# eib-64-intan-hs.net
KiCad netlist of a schematic drawn in EAGLE
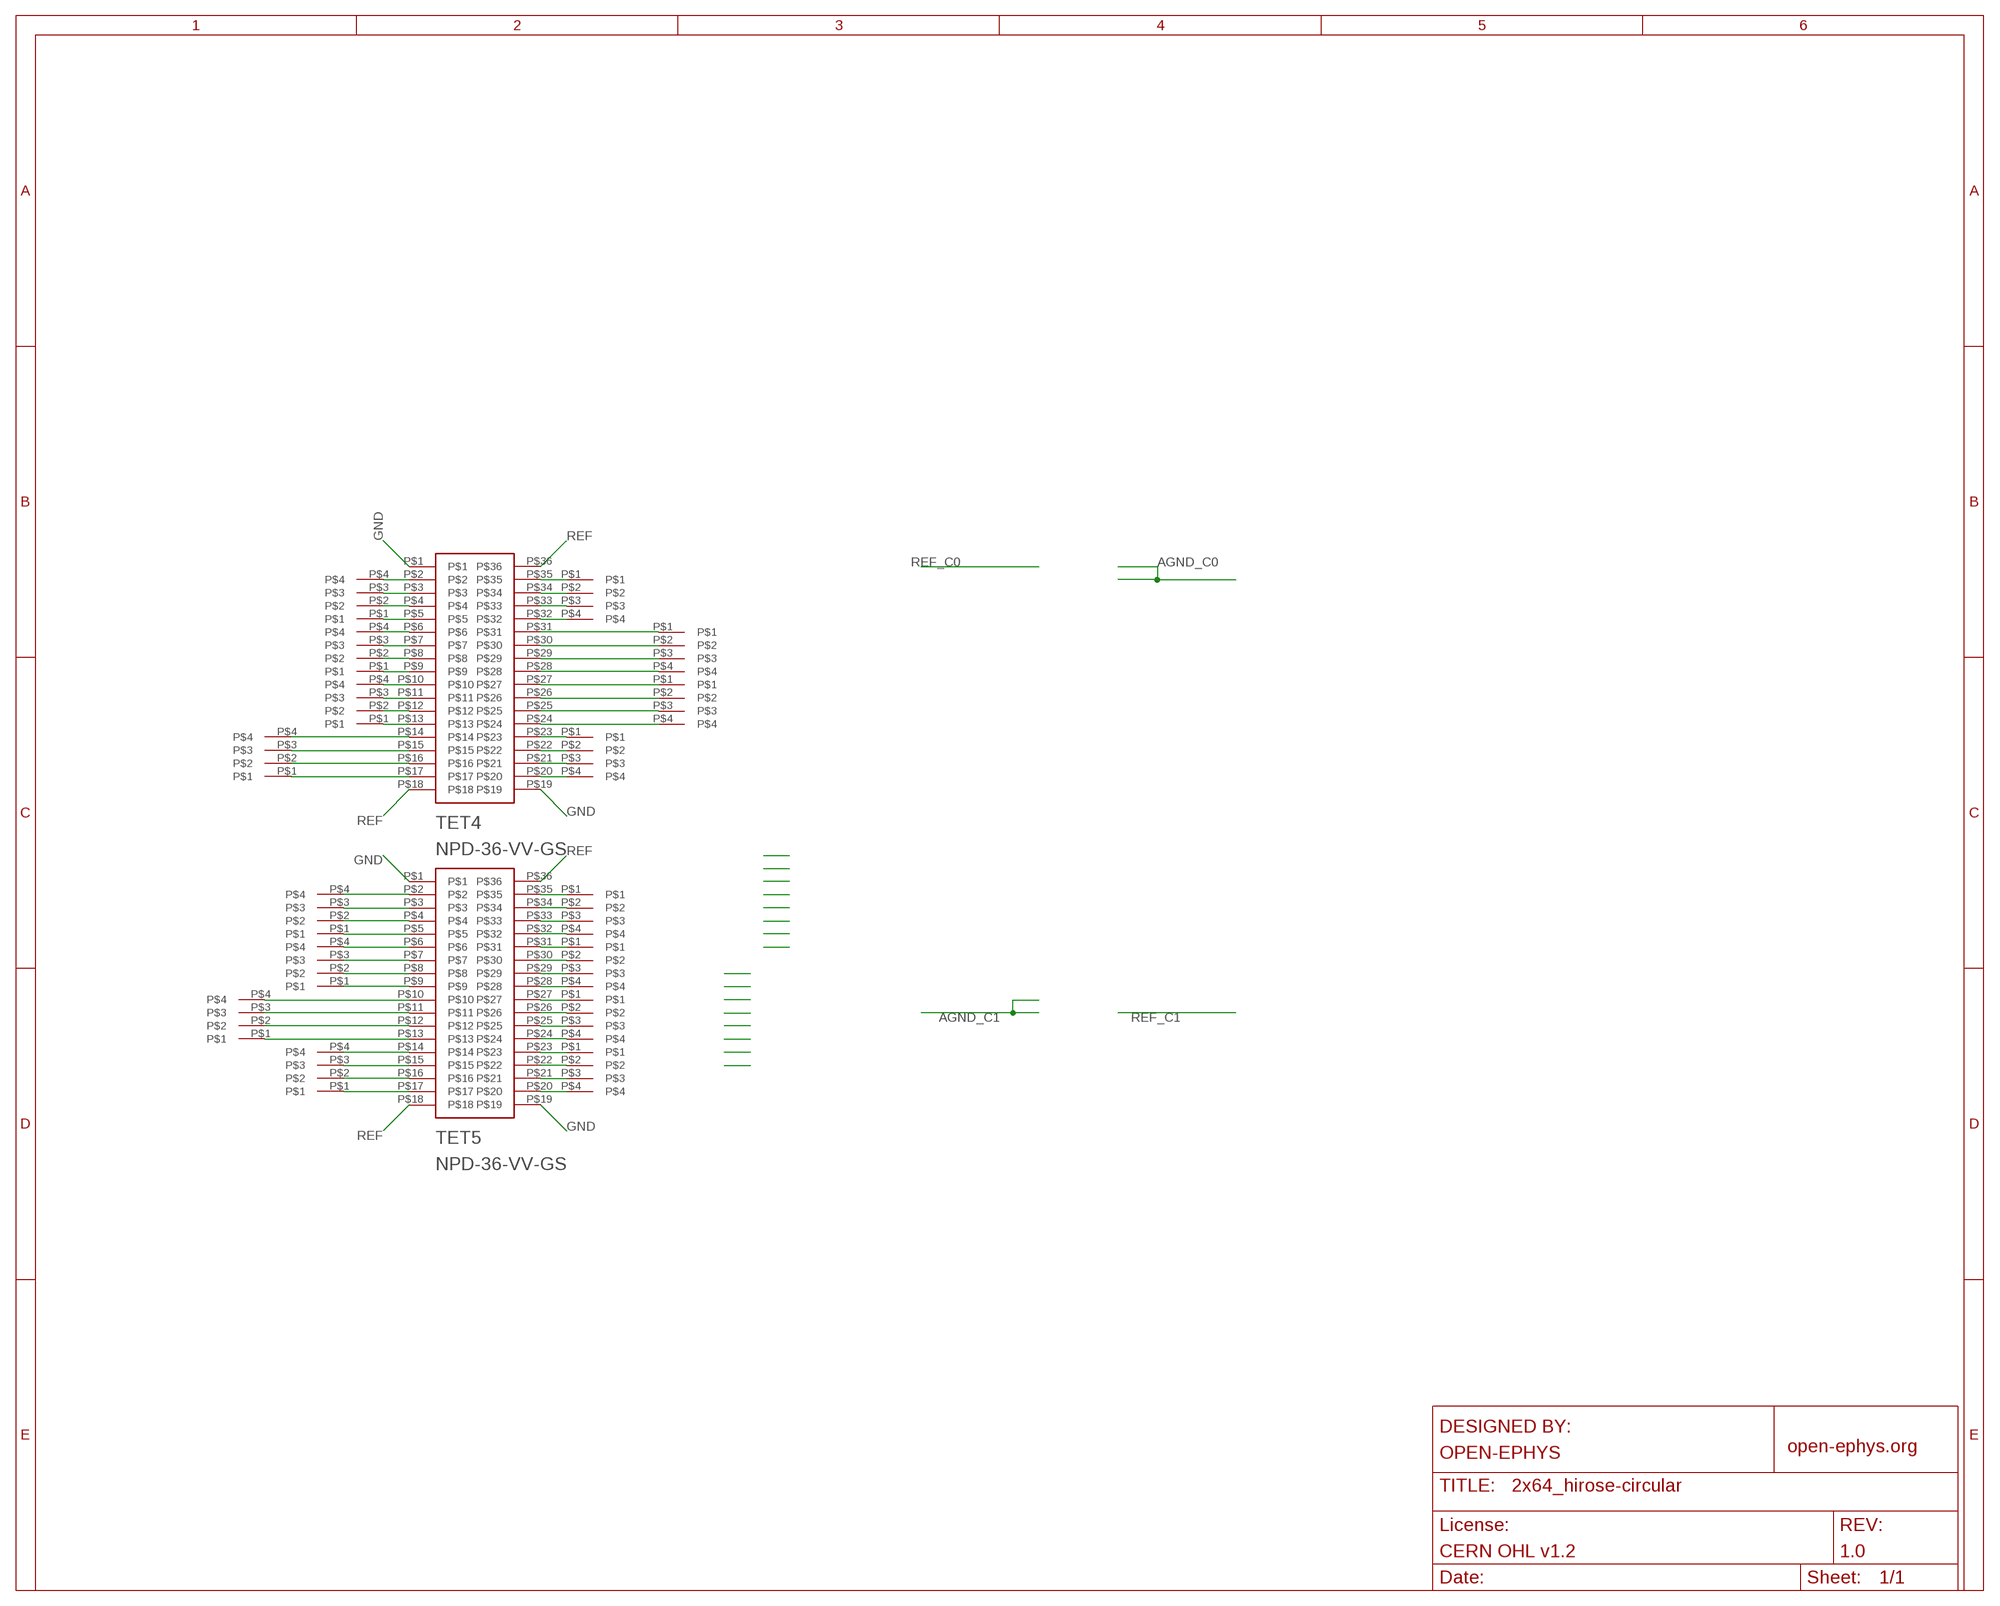
[diagram p0: schematic, sheet 1]

(export (version "E")
  (design (tool "Eeschema 10.0.6"))
  (components
    (comp (ref "TET0")
      (value "0")
      (footprint "eagle-import:TET32")
      (libsource (lib "eagle-import") (part "TET32"))
    )
    (comp (ref "TET1")
      (value "1")
      (footprint "eagle-import:TET32")
      (libsource (lib "eagle-import") (part "TET32"))
    )
    (comp (ref "TET2")
      (value "2")
      (footprint "eagle-import:TET32")
      (libsource (lib "eagle-import") (part "TET32"))
    )
    (comp (ref "TET3")
      (value "3")
      (footprint "eagle-import:TET32")
      (libsource (lib "eagle-import") (part "TET32"))
    )
    (comp (ref "TET4")
      (value "NPD-36-VV-GS")
      (footprint "eagle-import:NPD-36-VV-GS")
      (libsource (lib "eagle-import") (part "NPD-36-VV-GS"))
    )
    (comp (ref "TET5")
      (value "NPD-36-VV-GS")
      (footprint "eagle-import:NPD-36-VV-GS")
      (libsource (lib "eagle-import") (part "NPD-36-VV-GS"))
    )
    (comp (ref "TET8")
      (value "8")
      (footprint "eagle-import:TET32")
      (libsource (lib "eagle-import") (part "TET32"))
    )
    (comp (ref "TET9")
      (value "9")
      (footprint "eagle-import:TET32")
      (libsource (lib "eagle-import") (part "TET32"))
    )
    (comp (ref "TET10")
      (value "10")
      (footprint "eagle-import:TET32")
      (libsource (lib "eagle-import") (part "TET32"))
    )
    (comp (ref "TET11")
      (value "11")
      (footprint "eagle-import:TET32")
      (libsource (lib "eagle-import") (part "TET32"))
    )
    (comp (ref "TET12")
      (value "12")
      (footprint "eagle-import:TET32")
      (libsource (lib "eagle-import") (part "TET32"))
    )
    (comp (ref "TET13")
      (value "13")
      (footprint "eagle-import:TET32")
      (libsource (lib "eagle-import") (part "TET32"))
    )
    (comp (ref "TET14")
      (value "14")
      (footprint "eagle-import:TET32")
      (libsource (lib "eagle-import") (part "TET32"))
    )
    (comp (ref "TET15")
      (value "15")
      (footprint "eagle-import:TET32")
      (libsource (lib "eagle-import") (part "TET32"))
    )
    (comp (ref "TET20")
      (value "20")
      (footprint "eagle-import:TET32")
      (libsource (lib "eagle-import") (part "TET32"))
    )
    (comp (ref "TET21")
      (value "21")
      (footprint "eagle-import:TET32")
      (libsource (lib "eagle-import") (part "TET32"))
    )
    (comp (ref "TET22")
      (value "22")
      (footprint "eagle-import:TET32")
      (libsource (lib "eagle-import") (part "TET32"))
    )
    (comp (ref "TET23")
      (value "23")
      (footprint "eagle-import:TET32")
      (libsource (lib "eagle-import") (part "TET32"))
    )
  )
  (nets
    (net (code "3") (name "/GND") (class "Default")
      (node (ref "TET4") (pin "P$1") (pinfunction "P$1_P$1") (pintype "bidirectional"))
      (node (ref "TET4") (pin "P$19") (pinfunction "P$19_P$19") (pintype "bidirectional"))
      (node (ref "TET5") (pin "P$1") (pinfunction "P$1_P$1") (pintype "bidirectional"))
      (node (ref "TET5") (pin "P$19") (pinfunction "P$19_P$19") (pintype "bidirectional"))
    )
    (net (code "4") (name "/REF") (class "Default")
      (node (ref "TET4") (pin "P$18") (pinfunction "P$18_P$18") (pintype "bidirectional"))
      (node (ref "TET4") (pin "P$36") (pinfunction "P$36_P$36") (pintype "bidirectional"))
      (node (ref "TET5") (pin "P$18") (pinfunction "P$18_P$18") (pintype "bidirectional"))
      (node (ref "TET5") (pin "P$36") (pinfunction "P$36_P$36") (pintype "bidirectional"))
    )
    (net (code "7") (name "Net-(TET0-PadP$1)") (class "Default")
      (node (ref "TET0") (pin "P$1") (pinfunction "P$1_P$1") (pintype "bidirectional"))
      (node (ref "TET4") (pin "P$9") (pinfunction "P$9_P$9") (pintype "bidirectional"))
    )
    (net (code "8") (name "Net-(TET0-PadP$2)") (class "Default")
      (node (ref "TET0") (pin "P$2") (pinfunction "P$2_P$2") (pintype "bidirectional"))
      (node (ref "TET4") (pin "P$8") (pinfunction "P$8_P$8") (pintype "bidirectional"))
    )
    (net (code "9") (name "Net-(TET0-PadP$3)") (class "Default")
      (node (ref "TET0") (pin "P$3") (pinfunction "P$3_P$3") (pintype "bidirectional"))
      (node (ref "TET4") (pin "P$7") (pinfunction "P$7_P$7") (pintype "bidirectional"))
    )
    (net (code "10") (name "Net-(TET0-PadP$4)") (class "Default")
      (node (ref "TET0") (pin "P$4") (pinfunction "P$4_P$4") (pintype "bidirectional"))
      (node (ref "TET4") (pin "P$6") (pinfunction "P$6_P$6") (pintype "bidirectional"))
    )
    (net (code "11") (name "Net-(TET1-PadP$1)") (class "Default")
      (node (ref "TET1") (pin "P$1") (pinfunction "P$1_P$1") (pintype "bidirectional"))
      (node (ref "TET4") (pin "P$5") (pinfunction "P$5_P$5") (pintype "bidirectional"))
    )
    (net (code "12") (name "Net-(TET1-PadP$2)") (class "Default")
      (node (ref "TET1") (pin "P$2") (pinfunction "P$2_P$2") (pintype "bidirectional"))
      (node (ref "TET4") (pin "P$4") (pinfunction "P$4_P$4") (pintype "bidirectional"))
    )
    (net (code "13") (name "Net-(TET1-PadP$3)") (class "Default")
      (node (ref "TET1") (pin "P$3") (pinfunction "P$3_P$3") (pintype "bidirectional"))
      (node (ref "TET4") (pin "P$3") (pinfunction "P$3_P$3") (pintype "bidirectional"))
    )
    (net (code "14") (name "Net-(TET1-PadP$4)") (class "Default")
      (node (ref "TET1") (pin "P$4") (pinfunction "P$4_P$4") (pintype "bidirectional"))
      (node (ref "TET4") (pin "P$2") (pinfunction "P$2_P$2") (pintype "bidirectional"))
    )
    (net (code "15") (name "Net-(TET2-PadP$1)") (class "Default")
      (node (ref "TET2") (pin "P$1") (pinfunction "P$1_P$1") (pintype "bidirectional"))
      (node (ref "TET4") (pin "P$31") (pinfunction "P$31_P$31") (pintype "bidirectional"))
    )
    (net (code "16") (name "Net-(TET2-PadP$2)") (class "Default")
      (node (ref "TET2") (pin "P$2") (pinfunction "P$2_P$2") (pintype "bidirectional"))
      (node (ref "TET4") (pin "P$30") (pinfunction "P$30_P$30") (pintype "bidirectional"))
    )
    (net (code "17") (name "Net-(TET2-PadP$3)") (class "Default")
      (node (ref "TET2") (pin "P$3") (pinfunction "P$3_P$3") (pintype "bidirectional"))
      (node (ref "TET4") (pin "P$29") (pinfunction "P$29_P$29") (pintype "bidirectional"))
    )
    (net (code "18") (name "Net-(TET2-PadP$4)") (class "Default")
      (node (ref "TET2") (pin "P$4") (pinfunction "P$4_P$4") (pintype "bidirectional"))
      (node (ref "TET4") (pin "P$28") (pinfunction "P$28_P$28") (pintype "bidirectional"))
    )
    (net (code "19") (name "Net-(TET3-PadP$1)") (class "Default")
      (node (ref "TET3") (pin "P$1") (pinfunction "P$1_P$1") (pintype "bidirectional"))
      (node (ref "TET4") (pin "P$35") (pinfunction "P$35_P$35") (pintype "bidirectional"))
    )
    (net (code "20") (name "Net-(TET3-PadP$2)") (class "Default")
      (node (ref "TET3") (pin "P$2") (pinfunction "P$2_P$2") (pintype "bidirectional"))
      (node (ref "TET4") (pin "P$34") (pinfunction "P$34_P$34") (pintype "bidirectional"))
    )
    (net (code "21") (name "Net-(TET3-PadP$3)") (class "Default")
      (node (ref "TET3") (pin "P$3") (pinfunction "P$3_P$3") (pintype "bidirectional"))
      (node (ref "TET4") (pin "P$33") (pinfunction "P$33_P$33") (pintype "bidirectional"))
    )
    (net (code "22") (name "Net-(TET3-PadP$4)") (class "Default")
      (node (ref "TET3") (pin "P$4") (pinfunction "P$4_P$4") (pintype "bidirectional"))
      (node (ref "TET4") (pin "P$32") (pinfunction "P$32_P$32") (pintype "bidirectional"))
    )
    (net (code "23") (name "Net-(TET5-PadP$2)") (class "Default")
      (node (ref "TET5") (pin "P$2") (pinfunction "P$2_P$2") (pintype "bidirectional"))
      (node (ref "TET8") (pin "P$4") (pinfunction "P$4_P$4") (pintype "bidirectional"))
    )
    (net (code "24") (name "Net-(TET5-PadP$3)") (class "Default")
      (node (ref "TET5") (pin "P$3") (pinfunction "P$3_P$3") (pintype "bidirectional"))
      (node (ref "TET8") (pin "P$3") (pinfunction "P$3_P$3") (pintype "bidirectional"))
    )
    (net (code "25") (name "Net-(TET5-PadP$4)") (class "Default")
      (node (ref "TET5") (pin "P$4") (pinfunction "P$4_P$4") (pintype "bidirectional"))
      (node (ref "TET8") (pin "P$2") (pinfunction "P$2_P$2") (pintype "bidirectional"))
    )
    (net (code "26") (name "Net-(TET5-PadP$5)") (class "Default")
      (node (ref "TET5") (pin "P$5") (pinfunction "P$5_P$5") (pintype "bidirectional"))
      (node (ref "TET8") (pin "P$1") (pinfunction "P$1_P$1") (pintype "bidirectional"))
    )
    (net (code "27") (name "Net-(TET5-PadP$6)") (class "Default")
      (node (ref "TET5") (pin "P$6") (pinfunction "P$6_P$6") (pintype "bidirectional"))
      (node (ref "TET9") (pin "P$4") (pinfunction "P$4_P$4") (pintype "bidirectional"))
    )
    (net (code "28") (name "Net-(TET5-PadP$7)") (class "Default")
      (node (ref "TET5") (pin "P$7") (pinfunction "P$7_P$7") (pintype "bidirectional"))
      (node (ref "TET9") (pin "P$3") (pinfunction "P$3_P$3") (pintype "bidirectional"))
    )
    (net (code "29") (name "Net-(TET5-PadP$8)") (class "Default")
      (node (ref "TET5") (pin "P$8") (pinfunction "P$8_P$8") (pintype "bidirectional"))
      (node (ref "TET9") (pin "P$2") (pinfunction "P$2_P$2") (pintype "bidirectional"))
    )
    (net (code "30") (name "Net-(TET5-PadP$9)") (class "Default")
      (node (ref "TET5") (pin "P$9") (pinfunction "P$9_P$9") (pintype "bidirectional"))
      (node (ref "TET9") (pin "P$1") (pinfunction "P$1_P$1") (pintype "bidirectional"))
    )
    (net (code "31") (name "Net-(TET10-PadP$1)") (class "Default")
      (node (ref "TET10") (pin "P$1") (pinfunction "P$1_P$1") (pintype "bidirectional"))
      (node (ref "TET5") (pin "P$35") (pinfunction "P$35_P$35") (pintype "bidirectional"))
    )
    (net (code "32") (name "Net-(TET10-PadP$2)") (class "Default")
      (node (ref "TET10") (pin "P$2") (pinfunction "P$2_P$2") (pintype "bidirectional"))
      (node (ref "TET5") (pin "P$34") (pinfunction "P$34_P$34") (pintype "bidirectional"))
    )
    (net (code "33") (name "Net-(TET10-PadP$3)") (class "Default")
      (node (ref "TET10") (pin "P$3") (pinfunction "P$3_P$3") (pintype "bidirectional"))
      (node (ref "TET5") (pin "P$33") (pinfunction "P$33_P$33") (pintype "bidirectional"))
    )
    (net (code "34") (name "Net-(TET10-PadP$4)") (class "Default")
      (node (ref "TET10") (pin "P$4") (pinfunction "P$4_P$4") (pintype "bidirectional"))
      (node (ref "TET5") (pin "P$32") (pinfunction "P$32_P$32") (pintype "bidirectional"))
    )
    (net (code "35") (name "Net-(TET11-PadP$1)") (class "Default")
      (node (ref "TET11") (pin "P$1") (pinfunction "P$1_P$1") (pintype "bidirectional"))
      (node (ref "TET5") (pin "P$31") (pinfunction "P$31_P$31") (pintype "bidirectional"))
    )
    (net (code "36") (name "Net-(TET11-PadP$2)") (class "Default")
      (node (ref "TET11") (pin "P$2") (pinfunction "P$2_P$2") (pintype "bidirectional"))
      (node (ref "TET5") (pin "P$30") (pinfunction "P$30_P$30") (pintype "bidirectional"))
    )
    (net (code "37") (name "Net-(TET11-PadP$3)") (class "Default")
      (node (ref "TET11") (pin "P$3") (pinfunction "P$3_P$3") (pintype "bidirectional"))
      (node (ref "TET5") (pin "P$29") (pinfunction "P$29_P$29") (pintype "bidirectional"))
    )
    (net (code "38") (name "Net-(TET11-PadP$4)") (class "Default")
      (node (ref "TET11") (pin "P$4") (pinfunction "P$4_P$4") (pintype "bidirectional"))
      (node (ref "TET5") (pin "P$28") (pinfunction "P$28_P$28") (pintype "bidirectional"))
    )
    (net (code "39") (name "Net-(TET12-PadP$1)") (class "Default")
      (node (ref "TET12") (pin "P$1") (pinfunction "P$1_P$1") (pintype "bidirectional"))
      (node (ref "TET5") (pin "P$27") (pinfunction "P$27_P$27") (pintype "bidirectional"))
    )
    (net (code "40") (name "Net-(TET12-PadP$2)") (class "Default")
      (node (ref "TET12") (pin "P$2") (pinfunction "P$2_P$2") (pintype "bidirectional"))
      (node (ref "TET5") (pin "P$26") (pinfunction "P$26_P$26") (pintype "bidirectional"))
    )
    (net (code "41") (name "Net-(TET12-PadP$3)") (class "Default")
      (node (ref "TET12") (pin "P$3") (pinfunction "P$3_P$3") (pintype "bidirectional"))
      (node (ref "TET5") (pin "P$25") (pinfunction "P$25_P$25") (pintype "bidirectional"))
    )
    (net (code "42") (name "Net-(TET12-PadP$4)") (class "Default")
      (node (ref "TET12") (pin "P$4") (pinfunction "P$4_P$4") (pintype "bidirectional"))
      (node (ref "TET5") (pin "P$24") (pinfunction "P$24_P$24") (pintype "bidirectional"))
    )
    (net (code "43") (name "Net-(TET13-PadP$1)") (class "Default")
      (node (ref "TET13") (pin "P$1") (pinfunction "P$1_P$1") (pintype "bidirectional"))
      (node (ref "TET5") (pin "P$23") (pinfunction "P$23_P$23") (pintype "bidirectional"))
    )
    (net (code "44") (name "Net-(TET13-PadP$2)") (class "Default")
      (node (ref "TET13") (pin "P$2") (pinfunction "P$2_P$2") (pintype "bidirectional"))
      (node (ref "TET5") (pin "P$22") (pinfunction "P$22_P$22") (pintype "bidirectional"))
    )
    (net (code "45") (name "Net-(TET13-PadP$3)") (class "Default")
      (node (ref "TET13") (pin "P$3") (pinfunction "P$3_P$3") (pintype "bidirectional"))
      (node (ref "TET5") (pin "P$21") (pinfunction "P$21_P$21") (pintype "bidirectional"))
    )
    (net (code "46") (name "Net-(TET13-PadP$4)") (class "Default")
      (node (ref "TET13") (pin "P$4") (pinfunction "P$4_P$4") (pintype "bidirectional"))
      (node (ref "TET5") (pin "P$20") (pinfunction "P$20_P$20") (pintype "bidirectional"))
    )
    (net (code "47") (name "Net-(TET14-PadP$1)") (class "Default")
      (node (ref "TET14") (pin "P$1") (pinfunction "P$1_P$1") (pintype "bidirectional"))
      (node (ref "TET5") (pin "P$13") (pinfunction "P$13_P$13") (pintype "bidirectional"))
    )
    (net (code "48") (name "Net-(TET14-PadP$2)") (class "Default")
      (node (ref "TET14") (pin "P$2") (pinfunction "P$2_P$2") (pintype "bidirectional"))
      (node (ref "TET5") (pin "P$12") (pinfunction "P$12_P$12") (pintype "bidirectional"))
    )
    (net (code "49") (name "Net-(TET14-PadP$3)") (class "Default")
      (node (ref "TET14") (pin "P$3") (pinfunction "P$3_P$3") (pintype "bidirectional"))
      (node (ref "TET5") (pin "P$11") (pinfunction "P$11_P$11") (pintype "bidirectional"))
    )
    (net (code "50") (name "Net-(TET14-PadP$4)") (class "Default")
      (node (ref "TET14") (pin "P$4") (pinfunction "P$4_P$4") (pintype "bidirectional"))
      (node (ref "TET5") (pin "P$10") (pinfunction "P$10_P$10") (pintype "bidirectional"))
    )
    (net (code "51") (name "Net-(TET15-PadP$1)") (class "Default")
      (node (ref "TET15") (pin "P$1") (pinfunction "P$1_P$1") (pintype "bidirectional"))
      (node (ref "TET5") (pin "P$17") (pinfunction "P$17_P$17") (pintype "bidirectional"))
    )
    (net (code "52") (name "Net-(TET15-PadP$2)") (class "Default")
      (node (ref "TET15") (pin "P$2") (pinfunction "P$2_P$2") (pintype "bidirectional"))
      (node (ref "TET5") (pin "P$16") (pinfunction "P$16_P$16") (pintype "bidirectional"))
    )
    (net (code "53") (name "Net-(TET15-PadP$3)") (class "Default")
      (node (ref "TET15") (pin "P$3") (pinfunction "P$3_P$3") (pintype "bidirectional"))
      (node (ref "TET5") (pin "P$15") (pinfunction "P$15_P$15") (pintype "bidirectional"))
    )
    (net (code "54") (name "Net-(TET15-PadP$4)") (class "Default")
      (node (ref "TET15") (pin "P$4") (pinfunction "P$4_P$4") (pintype "bidirectional"))
      (node (ref "TET5") (pin "P$14") (pinfunction "P$14_P$14") (pintype "bidirectional"))
    )
    (net (code "55") (name "Net-(TET20-PadP$1)") (class "Default")
      (node (ref "TET20") (pin "P$1") (pinfunction "P$1_P$1") (pintype "bidirectional"))
      (node (ref "TET4") (pin "P$23") (pinfunction "P$23_P$23") (pintype "bidirectional"))
    )
    (net (code "56") (name "Net-(TET20-PadP$2)") (class "Default")
      (node (ref "TET20") (pin "P$2") (pinfunction "P$2_P$2") (pintype "bidirectional"))
      (node (ref "TET4") (pin "P$22") (pinfunction "P$22_P$22") (pintype "bidirectional"))
    )
    (net (code "57") (name "Net-(TET20-PadP$3)") (class "Default")
      (node (ref "TET20") (pin "P$3") (pinfunction "P$3_P$3") (pintype "bidirectional"))
      (node (ref "TET4") (pin "P$21") (pinfunction "P$21_P$21") (pintype "bidirectional"))
    )
    (net (code "58") (name "Net-(TET20-PadP$4)") (class "Default")
      (node (ref "TET20") (pin "P$4") (pinfunction "P$4_P$4") (pintype "bidirectional"))
      (node (ref "TET4") (pin "P$20") (pinfunction "P$20_P$20") (pintype "bidirectional"))
    )
    (net (code "59") (name "Net-(TET21-PadP$1)") (class "Default")
      (node (ref "TET21") (pin "P$1") (pinfunction "P$1_P$1") (pintype "bidirectional"))
      (node (ref "TET4") (pin "P$27") (pinfunction "P$27_P$27") (pintype "bidirectional"))
    )
    (net (code "60") (name "Net-(TET21-PadP$2)") (class "Default")
      (node (ref "TET21") (pin "P$2") (pinfunction "P$2_P$2") (pintype "bidirectional"))
      (node (ref "TET4") (pin "P$26") (pinfunction "P$26_P$26") (pintype "bidirectional"))
    )
    (net (code "61") (name "Net-(TET21-PadP$3)") (class "Default")
      (node (ref "TET21") (pin "P$3") (pinfunction "P$3_P$3") (pintype "bidirectional"))
      (node (ref "TET4") (pin "P$25") (pinfunction "P$25_P$25") (pintype "bidirectional"))
    )
    (net (code "62") (name "Net-(TET21-PadP$4)") (class "Default")
      (node (ref "TET21") (pin "P$4") (pinfunction "P$4_P$4") (pintype "bidirectional"))
      (node (ref "TET4") (pin "P$24") (pinfunction "P$24_P$24") (pintype "bidirectional"))
    )
    (net (code "63") (name "Net-(TET22-PadP$1)") (class "Default")
      (node (ref "TET22") (pin "P$1") (pinfunction "P$1_P$1") (pintype "bidirectional"))
      (node (ref "TET4") (pin "P$17") (pinfunction "P$17_P$17") (pintype "bidirectional"))
    )
    (net (code "64") (name "Net-(TET22-PadP$2)") (class "Default")
      (node (ref "TET22") (pin "P$2") (pinfunction "P$2_P$2") (pintype "bidirectional"))
      (node (ref "TET4") (pin "P$16") (pinfunction "P$16_P$16") (pintype "bidirectional"))
    )
    (net (code "65") (name "Net-(TET22-PadP$3)") (class "Default")
      (node (ref "TET22") (pin "P$3") (pinfunction "P$3_P$3") (pintype "bidirectional"))
      (node (ref "TET4") (pin "P$15") (pinfunction "P$15_P$15") (pintype "bidirectional"))
    )
    (net (code "66") (name "Net-(TET22-PadP$4)") (class "Default")
      (node (ref "TET22") (pin "P$4") (pinfunction "P$4_P$4") (pintype "bidirectional"))
      (node (ref "TET4") (pin "P$14") (pinfunction "P$14_P$14") (pintype "bidirectional"))
    )
    (net (code "67") (name "Net-(TET23-PadP$1)") (class "Default")
      (node (ref "TET23") (pin "P$1") (pinfunction "P$1_P$1") (pintype "bidirectional"))
      (node (ref "TET4") (pin "P$13") (pinfunction "P$13_P$13") (pintype "bidirectional"))
    )
    (net (code "68") (name "Net-(TET23-PadP$2)") (class "Default")
      (node (ref "TET23") (pin "P$2") (pinfunction "P$2_P$2") (pintype "bidirectional"))
      (node (ref "TET4") (pin "P$12") (pinfunction "P$12_P$12") (pintype "bidirectional"))
    )
    (net (code "69") (name "Net-(TET23-PadP$3)") (class "Default")
      (node (ref "TET23") (pin "P$3") (pinfunction "P$3_P$3") (pintype "bidirectional"))
      (node (ref "TET4") (pin "P$11") (pinfunction "P$11_P$11") (pintype "bidirectional"))
    )
    (net (code "70") (name "Net-(TET23-PadP$4)") (class "Default")
      (node (ref "TET23") (pin "P$4") (pinfunction "P$4_P$4") (pintype "bidirectional"))
      (node (ref "TET4") (pin "P$10") (pinfunction "P$10_P$10") (pintype "bidirectional"))
    )
  )
)
